# extraBoardv3.net
KiCad netlist of a schematic drawn in EasyEDA
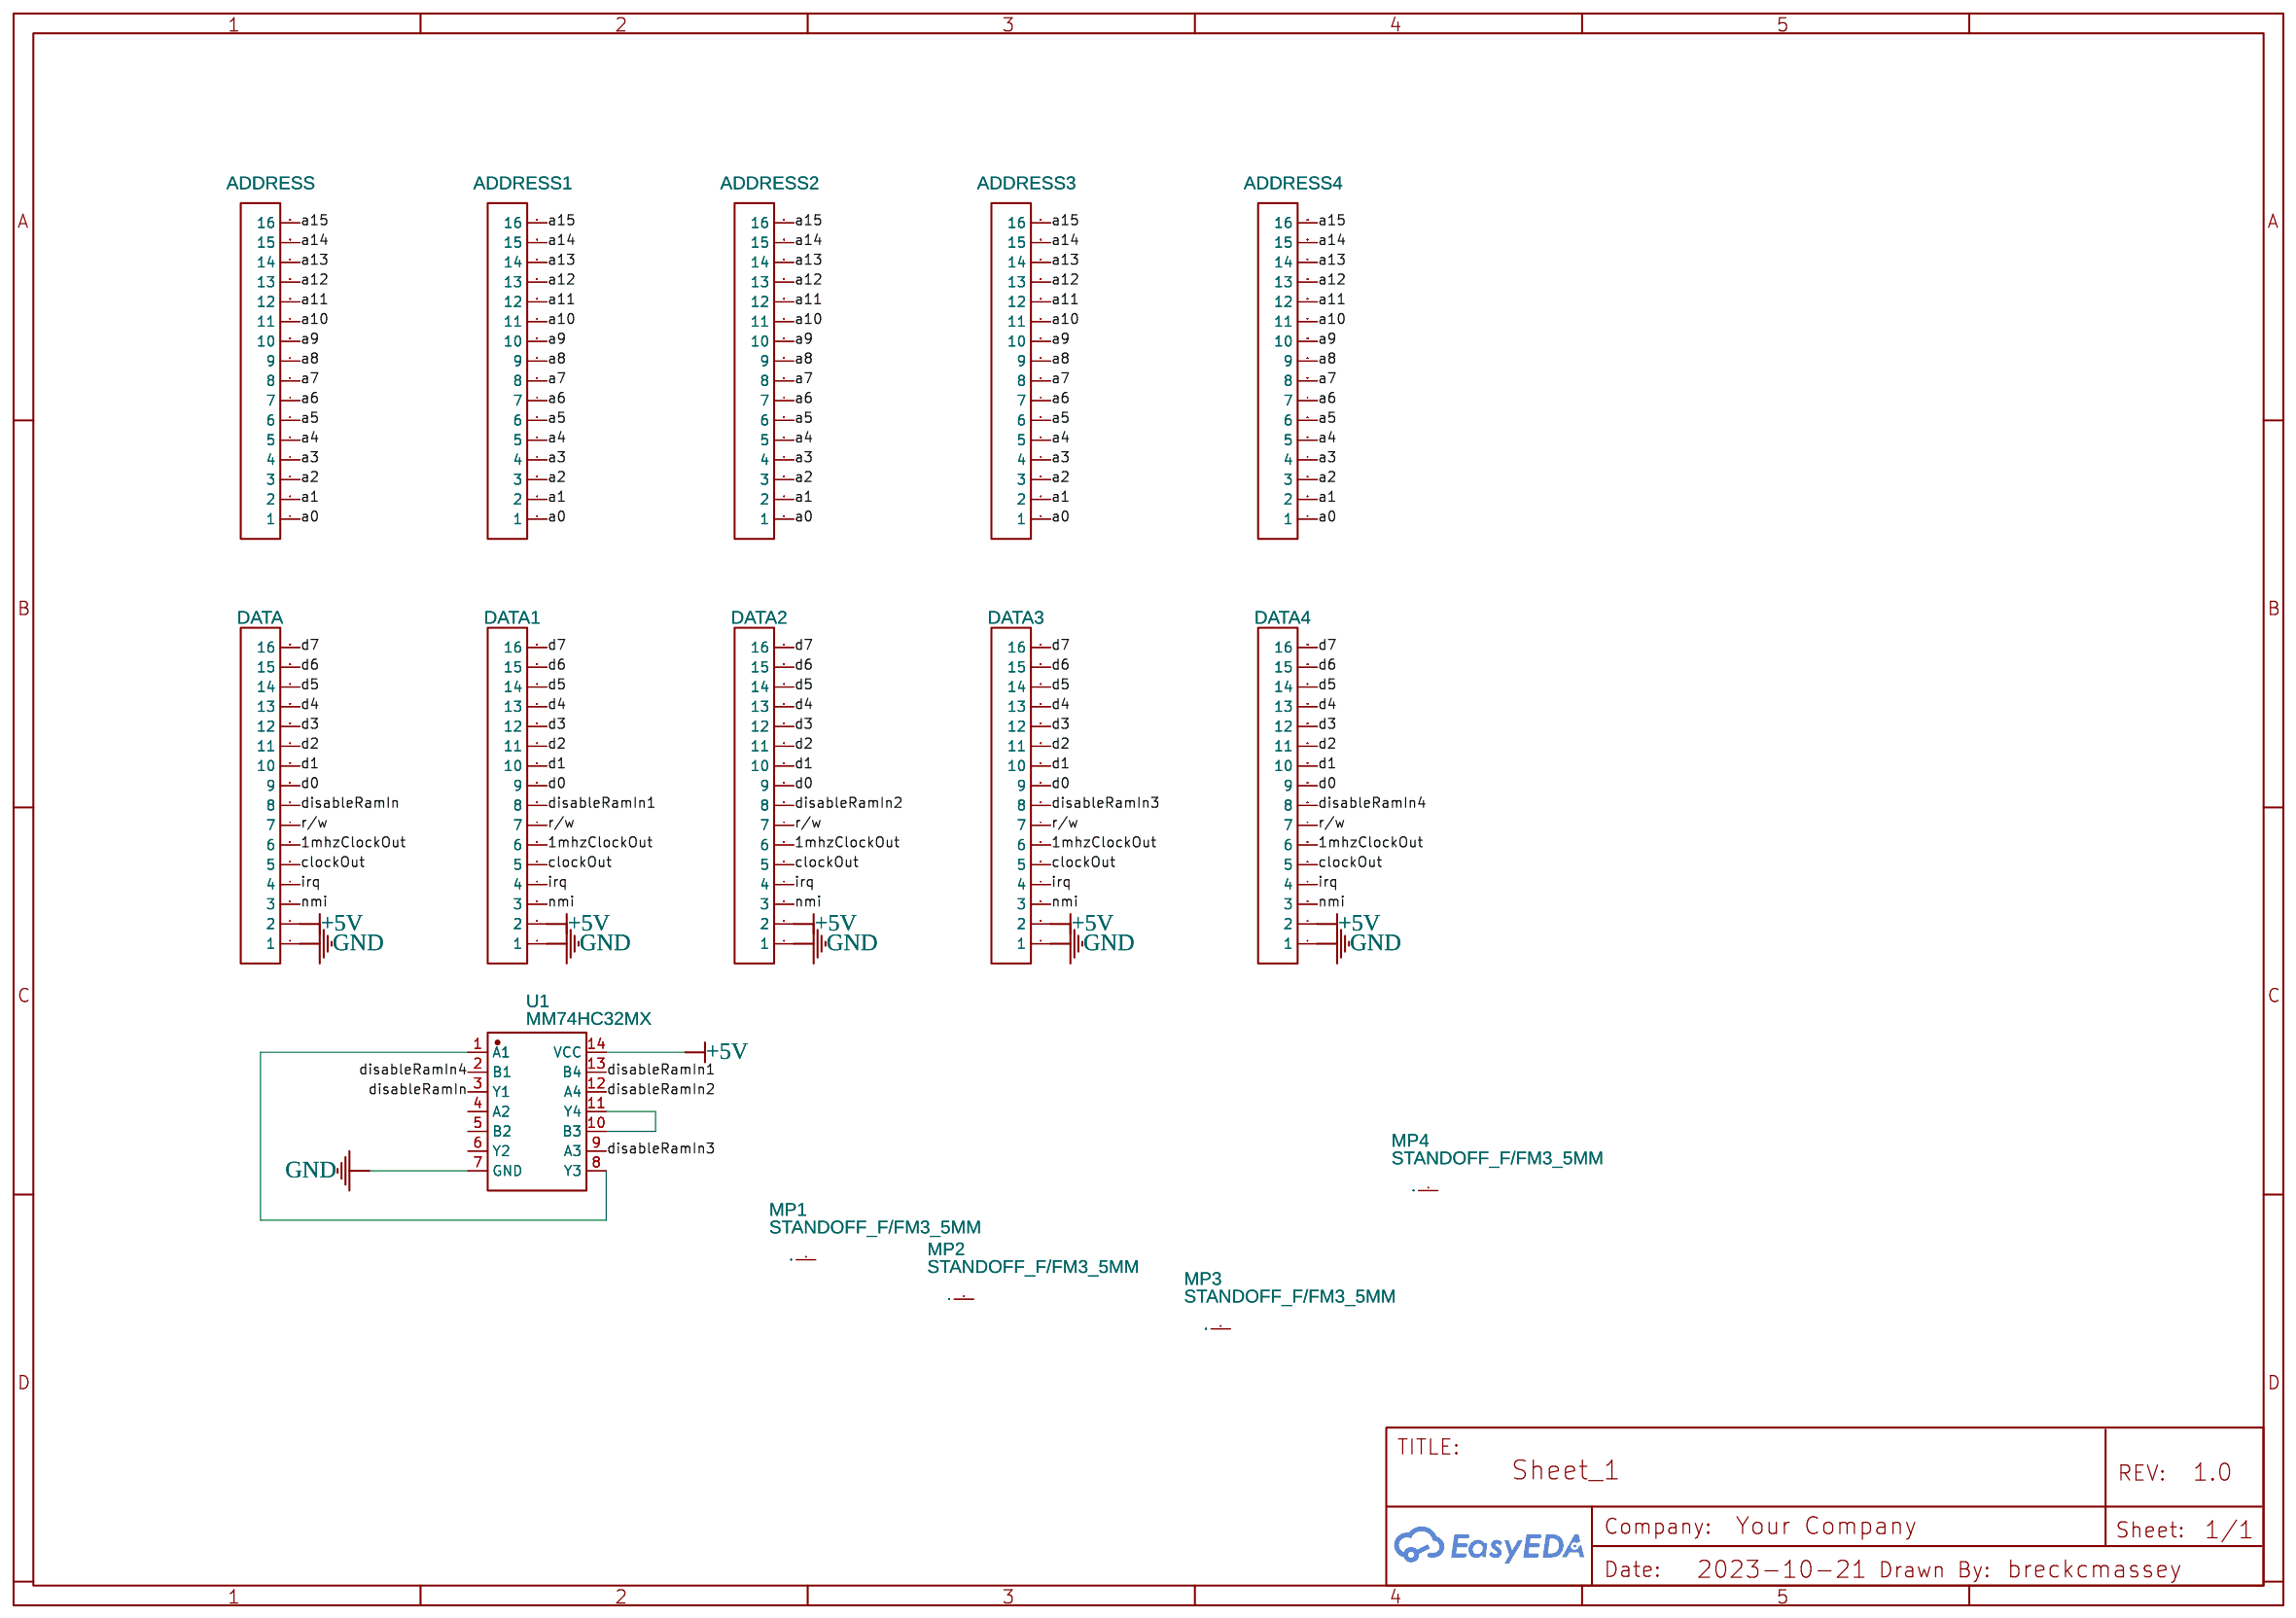
[diagram p0: schematic sheet]

(export (version "E")
  (design (tool "Eeschema 10.0.6"))
  (components
    (comp (ref "ADDRESS") (value "HDR-M-2.54_1x16") (libsource (lib "") (part "HDR-M-2.54_1x16")))
    (comp (ref "ADDRESS1") (value "HDR-M-2.54_1x16") (libsource (lib "") (part "HDR-M-2.54_1x16")))
    (comp (ref "ADDRESS2") (value "HDR-M-2.54_1x16") (libsource (lib "") (part "HDR-M-2.54_1x16")))
    (comp (ref "ADDRESS3") (value "HDR-M-2.54_1x16") (libsource (lib "") (part "HDR-M-2.54_1x16")))
    (comp (ref "ADDRESS4") (value "HDR-M-2.54_1x16") (libsource (lib "") (part "HDR-M-2.54_1x16")))
    (comp (ref "DATA") (value "HDR-M-2.54_1x16") (libsource (lib "") (part "HDR-M-2.54_1x16_1")))
    (comp (ref "DATA1") (value "HDR-M-2.54_1x16") (libsource (lib "") (part "HDR-M-2.54_1x16_1")))
    (comp (ref "DATA2") (value "HDR-M-2.54_1x16") (libsource (lib "") (part "HDR-M-2.54_1x16_1")))
    (comp (ref "DATA3") (value "HDR-M-2.54_1x16") (libsource (lib "") (part "HDR-M-2.54_1x16_1")))
    (comp (ref "DATA4") (value "HDR-M-2.54_1x16") (libsource (lib "") (part "HDR-M-2.54_1x16_1")))
    (comp (ref "MP1") (value "STANDOFF_F/FM3_5MM") (libsource (lib "") (part "STANDOFF_F/FM3_5MM")))
    (comp (ref "MP2") (value "STANDOFF_F/FM3_5MM") (libsource (lib "") (part "STANDOFF_F/FM3_5MM")))
    (comp (ref "MP3") (value "STANDOFF_F/FM3_5MM") (libsource (lib "") (part "STANDOFF_F/FM3_5MM")))
    (comp (ref "MP4") (value "STANDOFF_F/FM3_5MM") (libsource (lib "") (part "STANDOFF_F/FM3_5MM")))
    (comp (ref "U1")
      (value "MM74HC32MX")
      (fields (field (name "Manufacturer") "onsemi(安森美)"))
      (libsource (lib "") (part "MM74HC32MX"))
    )
  )
  (nets
    (net (code "1") (name "+5V") (class "Default")
      (node (ref "DATA") (pin "2") (pinfunction "2_2") (pintype "unspecified"))
      (node (ref "DATA1") (pin "2") (pinfunction "2_2") (pintype "unspecified"))
      (node (ref "DATA2") (pin "2") (pinfunction "2_2") (pintype "unspecified"))
      (node (ref "DATA3") (pin "2") (pinfunction "2_2") (pintype "unspecified"))
      (node (ref "DATA4") (pin "2") (pinfunction "2_2") (pintype "unspecified"))
      (node (ref "U1") (pin "14") (pinfunction "VCC_14") (pintype "unspecified"))
    )
    (net (code "2") (name "/1mhzClockOut") (class "Default")
      (node (ref "DATA") (pin "6") (pinfunction "6_6") (pintype "unspecified"))
      (node (ref "DATA1") (pin "6") (pinfunction "6_6") (pintype "unspecified"))
      (node (ref "DATA2") (pin "6") (pinfunction "6_6") (pintype "unspecified"))
      (node (ref "DATA3") (pin "6") (pinfunction "6_6") (pintype "unspecified"))
      (node (ref "DATA4") (pin "6") (pinfunction "6_6") (pintype "unspecified"))
    )
    (net (code "3") (name "/a0") (class "Default")
      (node (ref "ADDRESS") (pin "1") (pinfunction "1_1") (pintype "unspecified"))
      (node (ref "ADDRESS1") (pin "1") (pinfunction "1_1") (pintype "unspecified"))
      (node (ref "ADDRESS2") (pin "1") (pinfunction "1_1") (pintype "unspecified"))
      (node (ref "ADDRESS3") (pin "1") (pinfunction "1_1") (pintype "unspecified"))
      (node (ref "ADDRESS4") (pin "1") (pinfunction "1_1") (pintype "unspecified"))
    )
    (net (code "4") (name "/a1") (class "Default")
      (node (ref "ADDRESS") (pin "2") (pinfunction "2_2") (pintype "unspecified"))
      (node (ref "ADDRESS1") (pin "2") (pinfunction "2_2") (pintype "unspecified"))
      (node (ref "ADDRESS2") (pin "2") (pinfunction "2_2") (pintype "unspecified"))
      (node (ref "ADDRESS3") (pin "2") (pinfunction "2_2") (pintype "unspecified"))
      (node (ref "ADDRESS4") (pin "2") (pinfunction "2_2") (pintype "unspecified"))
    )
    (net (code "5") (name "/a2") (class "Default")
      (node (ref "ADDRESS") (pin "3") (pinfunction "3_3") (pintype "unspecified"))
      (node (ref "ADDRESS1") (pin "3") (pinfunction "3_3") (pintype "unspecified"))
      (node (ref "ADDRESS2") (pin "3") (pinfunction "3_3") (pintype "unspecified"))
      (node (ref "ADDRESS3") (pin "3") (pinfunction "3_3") (pintype "unspecified"))
      (node (ref "ADDRESS4") (pin "3") (pinfunction "3_3") (pintype "unspecified"))
    )
    (net (code "6") (name "/a3") (class "Default")
      (node (ref "ADDRESS") (pin "4") (pinfunction "4_4") (pintype "unspecified"))
      (node (ref "ADDRESS1") (pin "4") (pinfunction "4_4") (pintype "unspecified"))
      (node (ref "ADDRESS2") (pin "4") (pinfunction "4_4") (pintype "unspecified"))
      (node (ref "ADDRESS3") (pin "4") (pinfunction "4_4") (pintype "unspecified"))
      (node (ref "ADDRESS4") (pin "4") (pinfunction "4_4") (pintype "unspecified"))
    )
    (net (code "7") (name "/a4") (class "Default")
      (node (ref "ADDRESS") (pin "5") (pinfunction "5_5") (pintype "unspecified"))
      (node (ref "ADDRESS1") (pin "5") (pinfunction "5_5") (pintype "unspecified"))
      (node (ref "ADDRESS2") (pin "5") (pinfunction "5_5") (pintype "unspecified"))
      (node (ref "ADDRESS3") (pin "5") (pinfunction "5_5") (pintype "unspecified"))
      (node (ref "ADDRESS4") (pin "5") (pinfunction "5_5") (pintype "unspecified"))
    )
    (net (code "8") (name "/a5") (class "Default")
      (node (ref "ADDRESS") (pin "6") (pinfunction "6_6") (pintype "unspecified"))
      (node (ref "ADDRESS1") (pin "6") (pinfunction "6_6") (pintype "unspecified"))
      (node (ref "ADDRESS2") (pin "6") (pinfunction "6_6") (pintype "unspecified"))
      (node (ref "ADDRESS3") (pin "6") (pinfunction "6_6") (pintype "unspecified"))
      (node (ref "ADDRESS4") (pin "6") (pinfunction "6_6") (pintype "unspecified"))
    )
    (net (code "9") (name "/a6") (class "Default")
      (node (ref "ADDRESS") (pin "7") (pinfunction "7_7") (pintype "unspecified"))
      (node (ref "ADDRESS1") (pin "7") (pinfunction "7_7") (pintype "unspecified"))
      (node (ref "ADDRESS2") (pin "7") (pinfunction "7_7") (pintype "unspecified"))
      (node (ref "ADDRESS3") (pin "7") (pinfunction "7_7") (pintype "unspecified"))
      (node (ref "ADDRESS4") (pin "7") (pinfunction "7_7") (pintype "unspecified"))
    )
    (net (code "10") (name "/a7") (class "Default")
      (node (ref "ADDRESS") (pin "8") (pinfunction "8_8") (pintype "unspecified"))
      (node (ref "ADDRESS1") (pin "8") (pinfunction "8_8") (pintype "unspecified"))
      (node (ref "ADDRESS2") (pin "8") (pinfunction "8_8") (pintype "unspecified"))
      (node (ref "ADDRESS3") (pin "8") (pinfunction "8_8") (pintype "unspecified"))
      (node (ref "ADDRESS4") (pin "8") (pinfunction "8_8") (pintype "unspecified"))
    )
    (net (code "11") (name "/a8") (class "Default")
      (node (ref "ADDRESS") (pin "9") (pinfunction "9_9") (pintype "unspecified"))
      (node (ref "ADDRESS1") (pin "9") (pinfunction "9_9") (pintype "unspecified"))
      (node (ref "ADDRESS2") (pin "9") (pinfunction "9_9") (pintype "unspecified"))
      (node (ref "ADDRESS3") (pin "9") (pinfunction "9_9") (pintype "unspecified"))
      (node (ref "ADDRESS4") (pin "9") (pinfunction "9_9") (pintype "unspecified"))
    )
    (net (code "12") (name "/a9") (class "Default")
      (node (ref "ADDRESS") (pin "10") (pinfunction "10_10") (pintype "unspecified"))
      (node (ref "ADDRESS1") (pin "10") (pinfunction "10_10") (pintype "unspecified"))
      (node (ref "ADDRESS2") (pin "10") (pinfunction "10_10") (pintype "unspecified"))
      (node (ref "ADDRESS3") (pin "10") (pinfunction "10_10") (pintype "unspecified"))
      (node (ref "ADDRESS4") (pin "10") (pinfunction "10_10") (pintype "unspecified"))
    )
    (net (code "13") (name "/a10") (class "Default")
      (node (ref "ADDRESS") (pin "11") (pinfunction "11_11") (pintype "unspecified"))
      (node (ref "ADDRESS1") (pin "11") (pinfunction "11_11") (pintype "unspecified"))
      (node (ref "ADDRESS2") (pin "11") (pinfunction "11_11") (pintype "unspecified"))
      (node (ref "ADDRESS3") (pin "11") (pinfunction "11_11") (pintype "unspecified"))
      (node (ref "ADDRESS4") (pin "11") (pinfunction "11_11") (pintype "unspecified"))
    )
    (net (code "14") (name "/a11") (class "Default")
      (node (ref "ADDRESS") (pin "12") (pinfunction "12_12") (pintype "unspecified"))
      (node (ref "ADDRESS1") (pin "12") (pinfunction "12_12") (pintype "unspecified"))
      (node (ref "ADDRESS2") (pin "12") (pinfunction "12_12") (pintype "unspecified"))
      (node (ref "ADDRESS3") (pin "12") (pinfunction "12_12") (pintype "unspecified"))
      (node (ref "ADDRESS4") (pin "12") (pinfunction "12_12") (pintype "unspecified"))
    )
    (net (code "15") (name "/a12") (class "Default")
      (node (ref "ADDRESS") (pin "13") (pinfunction "13_13") (pintype "unspecified"))
      (node (ref "ADDRESS1") (pin "13") (pinfunction "13_13") (pintype "unspecified"))
      (node (ref "ADDRESS2") (pin "13") (pinfunction "13_13") (pintype "unspecified"))
      (node (ref "ADDRESS3") (pin "13") (pinfunction "13_13") (pintype "unspecified"))
      (node (ref "ADDRESS4") (pin "13") (pinfunction "13_13") (pintype "unspecified"))
    )
    (net (code "16") (name "/a13") (class "Default")
      (node (ref "ADDRESS") (pin "14") (pinfunction "14_14") (pintype "unspecified"))
      (node (ref "ADDRESS1") (pin "14") (pinfunction "14_14") (pintype "unspecified"))
      (node (ref "ADDRESS2") (pin "14") (pinfunction "14_14") (pintype "unspecified"))
      (node (ref "ADDRESS3") (pin "14") (pinfunction "14_14") (pintype "unspecified"))
      (node (ref "ADDRESS4") (pin "14") (pinfunction "14_14") (pintype "unspecified"))
    )
    (net (code "17") (name "/a14") (class "Default")
      (node (ref "ADDRESS") (pin "15") (pinfunction "15_15") (pintype "unspecified"))
      (node (ref "ADDRESS1") (pin "15") (pinfunction "15_15") (pintype "unspecified"))
      (node (ref "ADDRESS2") (pin "15") (pinfunction "15_15") (pintype "unspecified"))
      (node (ref "ADDRESS3") (pin "15") (pinfunction "15_15") (pintype "unspecified"))
      (node (ref "ADDRESS4") (pin "15") (pinfunction "15_15") (pintype "unspecified"))
    )
    (net (code "18") (name "/a15") (class "Default")
      (node (ref "ADDRESS") (pin "16") (pinfunction "16_16") (pintype "unspecified"))
      (node (ref "ADDRESS1") (pin "16") (pinfunction "16_16") (pintype "unspecified"))
      (node (ref "ADDRESS2") (pin "16") (pinfunction "16_16") (pintype "unspecified"))
      (node (ref "ADDRESS3") (pin "16") (pinfunction "16_16") (pintype "unspecified"))
      (node (ref "ADDRESS4") (pin "16") (pinfunction "16_16") (pintype "unspecified"))
    )
    (net (code "19") (name "/clockOut") (class "Default")
      (node (ref "DATA") (pin "5") (pinfunction "5_5") (pintype "unspecified"))
      (node (ref "DATA1") (pin "5") (pinfunction "5_5") (pintype "unspecified"))
      (node (ref "DATA2") (pin "5") (pinfunction "5_5") (pintype "unspecified"))
      (node (ref "DATA3") (pin "5") (pinfunction "5_5") (pintype "unspecified"))
      (node (ref "DATA4") (pin "5") (pinfunction "5_5") (pintype "unspecified"))
    )
    (net (code "20") (name "/d0") (class "Default")
      (node (ref "DATA") (pin "9") (pinfunction "9_9") (pintype "unspecified"))
      (node (ref "DATA1") (pin "9") (pinfunction "9_9") (pintype "unspecified"))
      (node (ref "DATA2") (pin "9") (pinfunction "9_9") (pintype "unspecified"))
      (node (ref "DATA3") (pin "9") (pinfunction "9_9") (pintype "unspecified"))
      (node (ref "DATA4") (pin "9") (pinfunction "9_9") (pintype "unspecified"))
    )
    (net (code "21") (name "/d1") (class "Default")
      (node (ref "DATA") (pin "10") (pinfunction "10_10") (pintype "unspecified"))
      (node (ref "DATA1") (pin "10") (pinfunction "10_10") (pintype "unspecified"))
      (node (ref "DATA2") (pin "10") (pinfunction "10_10") (pintype "unspecified"))
      (node (ref "DATA3") (pin "10") (pinfunction "10_10") (pintype "unspecified"))
      (node (ref "DATA4") (pin "10") (pinfunction "10_10") (pintype "unspecified"))
    )
    (net (code "22") (name "/d2") (class "Default")
      (node (ref "DATA") (pin "11") (pinfunction "11_11") (pintype "unspecified"))
      (node (ref "DATA1") (pin "11") (pinfunction "11_11") (pintype "unspecified"))
      (node (ref "DATA2") (pin "11") (pinfunction "11_11") (pintype "unspecified"))
      (node (ref "DATA3") (pin "11") (pinfunction "11_11") (pintype "unspecified"))
      (node (ref "DATA4") (pin "11") (pinfunction "11_11") (pintype "unspecified"))
    )
    (net (code "23") (name "/d3") (class "Default")
      (node (ref "DATA") (pin "12") (pinfunction "12_12") (pintype "unspecified"))
      (node (ref "DATA1") (pin "12") (pinfunction "12_12") (pintype "unspecified"))
      (node (ref "DATA2") (pin "12") (pinfunction "12_12") (pintype "unspecified"))
      (node (ref "DATA3") (pin "12") (pinfunction "12_12") (pintype "unspecified"))
      (node (ref "DATA4") (pin "12") (pinfunction "12_12") (pintype "unspecified"))
    )
    (net (code "24") (name "/d4") (class "Default")
      (node (ref "DATA") (pin "13") (pinfunction "13_13") (pintype "unspecified"))
      (node (ref "DATA1") (pin "13") (pinfunction "13_13") (pintype "unspecified"))
      (node (ref "DATA2") (pin "13") (pinfunction "13_13") (pintype "unspecified"))
      (node (ref "DATA3") (pin "13") (pinfunction "13_13") (pintype "unspecified"))
      (node (ref "DATA4") (pin "13") (pinfunction "13_13") (pintype "unspecified"))
    )
    (net (code "25") (name "/d5") (class "Default")
      (node (ref "DATA") (pin "14") (pinfunction "14_14") (pintype "unspecified"))
      (node (ref "DATA1") (pin "14") (pinfunction "14_14") (pintype "unspecified"))
      (node (ref "DATA2") (pin "14") (pinfunction "14_14") (pintype "unspecified"))
      (node (ref "DATA3") (pin "14") (pinfunction "14_14") (pintype "unspecified"))
      (node (ref "DATA4") (pin "14") (pinfunction "14_14") (pintype "unspecified"))
    )
    (net (code "26") (name "/d6") (class "Default")
      (node (ref "DATA") (pin "15") (pinfunction "15_15") (pintype "unspecified"))
      (node (ref "DATA1") (pin "15") (pinfunction "15_15") (pintype "unspecified"))
      (node (ref "DATA2") (pin "15") (pinfunction "15_15") (pintype "unspecified"))
      (node (ref "DATA3") (pin "15") (pinfunction "15_15") (pintype "unspecified"))
      (node (ref "DATA4") (pin "15") (pinfunction "15_15") (pintype "unspecified"))
    )
    (net (code "27") (name "/d7") (class "Default")
      (node (ref "DATA") (pin "16") (pinfunction "16_16") (pintype "unspecified"))
      (node (ref "DATA1") (pin "16") (pinfunction "16_16") (pintype "unspecified"))
      (node (ref "DATA2") (pin "16") (pinfunction "16_16") (pintype "unspecified"))
      (node (ref "DATA3") (pin "16") (pinfunction "16_16") (pintype "unspecified"))
      (node (ref "DATA4") (pin "16") (pinfunction "16_16") (pintype "unspecified"))
    )
    (net (code "28") (name "/disableRamIn") (class "Default")
      (node (ref "DATA") (pin "8") (pinfunction "8_8") (pintype "unspecified"))
      (node (ref "U1") (pin "3") (pinfunction "Y1_3") (pintype "unspecified"))
    )
    (net (code "29") (name "/disableRamIn1") (class "Default")
      (node (ref "DATA1") (pin "8") (pinfunction "8_8") (pintype "unspecified"))
      (node (ref "U1") (pin "13") (pinfunction "B4_13") (pintype "unspecified"))
    )
    (net (code "30") (name "/disableRamIn2") (class "Default")
      (node (ref "DATA2") (pin "8") (pinfunction "8_8") (pintype "unspecified"))
      (node (ref "U1") (pin "12") (pinfunction "A4_12") (pintype "unspecified"))
    )
    (net (code "31") (name "/disableRamIn3") (class "Default")
      (node (ref "DATA3") (pin "8") (pinfunction "8_8") (pintype "unspecified"))
      (node (ref "U1") (pin "9") (pinfunction "A3_9") (pintype "unspecified"))
    )
    (net (code "32") (name "/disableRamIn4") (class "Default")
      (node (ref "DATA4") (pin "8") (pinfunction "8_8") (pintype "unspecified"))
      (node (ref "U1") (pin "2") (pinfunction "B1_2") (pintype "unspecified"))
    )
    (net (code "33") (name "/irq") (class "Default")
      (node (ref "DATA") (pin "4") (pinfunction "4_4") (pintype "unspecified"))
      (node (ref "DATA1") (pin "4") (pinfunction "4_4") (pintype "unspecified"))
      (node (ref "DATA2") (pin "4") (pinfunction "4_4") (pintype "unspecified"))
      (node (ref "DATA3") (pin "4") (pinfunction "4_4") (pintype "unspecified"))
      (node (ref "DATA4") (pin "4") (pinfunction "4_4") (pintype "unspecified"))
    )
    (net (code "34") (name "/nmi") (class "Default")
      (node (ref "DATA") (pin "3") (pinfunction "3_3") (pintype "unspecified"))
      (node (ref "DATA1") (pin "3") (pinfunction "3_3") (pintype "unspecified"))
      (node (ref "DATA2") (pin "3") (pinfunction "3_3") (pintype "unspecified"))
      (node (ref "DATA3") (pin "3") (pinfunction "3_3") (pintype "unspecified"))
      (node (ref "DATA4") (pin "3") (pinfunction "3_3") (pintype "unspecified"))
    )
    (net (code "35") (name "/r{slash}w") (class "Default")
      (node (ref "DATA") (pin "7") (pinfunction "7_7") (pintype "unspecified"))
      (node (ref "DATA1") (pin "7") (pinfunction "7_7") (pintype "unspecified"))
      (node (ref "DATA2") (pin "7") (pinfunction "7_7") (pintype "unspecified"))
      (node (ref "DATA3") (pin "7") (pinfunction "7_7") (pintype "unspecified"))
      (node (ref "DATA4") (pin "7") (pinfunction "7_7") (pintype "unspecified"))
    )
    (net (code "36") (name "GND") (class "Default")
      (node (ref "DATA") (pin "1") (pinfunction "1_1") (pintype "unspecified"))
      (node (ref "DATA1") (pin "1") (pinfunction "1_1") (pintype "unspecified"))
      (node (ref "DATA2") (pin "1") (pinfunction "1_1") (pintype "unspecified"))
      (node (ref "DATA3") (pin "1") (pinfunction "1_1") (pintype "unspecified"))
      (node (ref "DATA4") (pin "1") (pinfunction "1_1") (pintype "unspecified"))
      (node (ref "U1") (pin "7") (pinfunction "GND_7") (pintype "unspecified"))
    )
    (net (code "37") (name "Net-(U1-A1)") (class "Default")
      (node (ref "U1") (pin "1") (pinfunction "A1_1") (pintype "unspecified"))
      (node (ref "U1") (pin "8") (pinfunction "Y3_8") (pintype "unspecified"))
    )
    (net (code "38") (name "Net-(U1-B3)") (class "Default")
      (node (ref "U1") (pin "10") (pinfunction "B3_10") (pintype "unspecified"))
      (node (ref "U1") (pin "11") (pinfunction "Y4_11") (pintype "unspecified"))
    )
    (net (code "39") (name "unconnected-(MP1-P$1-Pad1)") (class "Default")
      (node (ref "MP1") (pin "1") (pinfunction "P$1_1") (pintype "bidirectional"))
    )
    (net (code "40") (name "unconnected-(MP2-P$1-Pad1)") (class "Default")
      (node (ref "MP2") (pin "1") (pinfunction "P$1_1") (pintype "bidirectional"))
    )
    (net (code "41") (name "unconnected-(MP3-P$1-Pad1)") (class "Default")
      (node (ref "MP3") (pin "1") (pinfunction "P$1_1") (pintype "bidirectional"))
    )
    (net (code "42") (name "unconnected-(MP4-P$1-Pad1)") (class "Default")
      (node (ref "MP4") (pin "1") (pinfunction "P$1_1") (pintype "bidirectional"))
    )
    (net (code "43") (name "unconnected-(U1-A2-Pad4)") (class "Default")
      (node (ref "U1") (pin "4") (pinfunction "A2_4") (pintype "unspecified"))
    )
    (net (code "44") (name "unconnected-(U1-B2-Pad5)") (class "Default")
      (node (ref "U1") (pin "5") (pinfunction "B2_5") (pintype "unspecified"))
    )
    (net (code "45") (name "unconnected-(U1-Y2-Pad6)") (class "Default")
      (node (ref "U1") (pin "6") (pinfunction "Y2_6") (pintype "unspecified"))
    )
  )
)
